# 01-POWER_AC-DC.net
KiCad netlist of a schematic drawn in Altium Designer
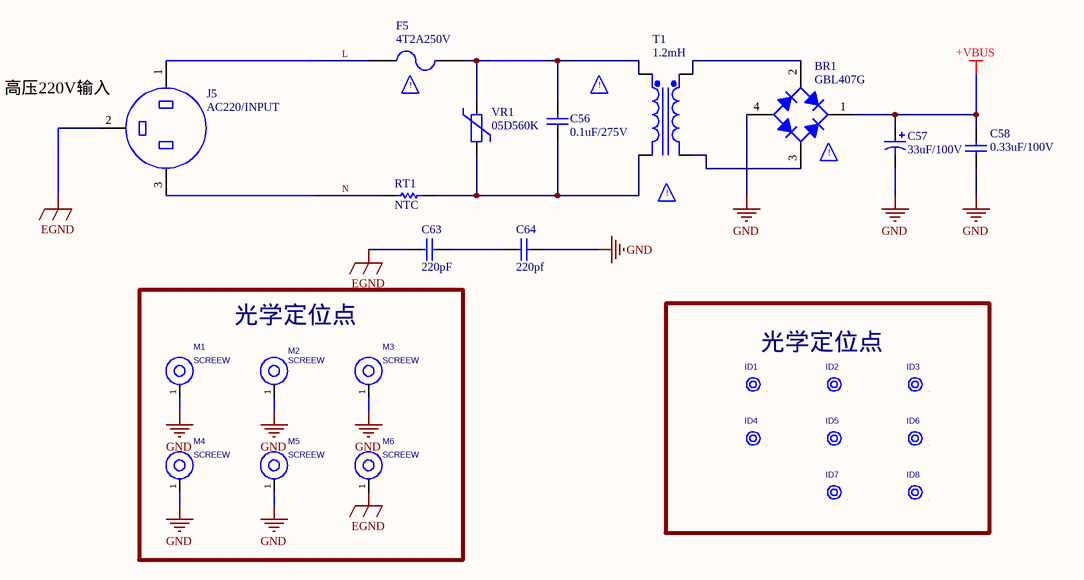
[diagram p0: 01-POWER AC-DC.SchDoc]

(export (version "E")
  (design (tool "Eeschema 10.0.6"))
  (components
    (comp (ref "BR1")
      (value "GBL407G")
      (footprint "GBL407G")
      (description "Full Wave Diode Bridge")
      (fields (field (name "ALTIUM_UNNAMED_1") "GBL407G") (field (name "PUBLISHER") "Altium Limited"))
      (libsource (lib "Miscellaneous Devices") (part "Bridge1"))
    )
    (comp (ref "C56")
      (value "0.1uF/275V")
      (footprint "CBB62-275VAC-104K")
      (description "Capacitor")
      (fields (field (name "Comment") "Cap") (field (name "PUBLISHER") "Altium Limited"))
      (libsource (lib "Miscellaneous Devices") (part "Cap"))
    )
    (comp (ref "C57")
      (value "33uF/100V")
      (footprint "CE16250SH1")
      (description "Polarized Capacitor (Radial)")
      (fields (field (name "PUBLISHER") "Altium Limited"))
      (libsource (lib "Miscellaneous Devices") (part "Cap Pol1"))
    )
    (comp (ref "C58")
      (value "0.33uF/100V")
      (footprint "AF334J1J079L270D9H")
      (description "Capacitor")
      (fields (field (name "Comment") "Cap") (field (name "PUBLISHER") "Altium Limited"))
      (libsource (lib "Miscellaneous Devices") (part "Cap"))
    )
    (comp (ref "C63")
      (value "220pF")
      (footprint "C0805")
      (description "Capacitor")
      (fields (field (name "Comment") "Cap") (field (name "PUBLISHER") "Altium Limited"))
      (libsource (lib "Lib") (part "Cap"))
    )
    (comp (ref "C64")
      (value "220pf")
      (footprint "C0805")
      (description "Capacitor")
      (fields (field (name "Comment") "Cap") (field (name "PUBLISHER") "Altium Limited"))
      (libsource (lib "Lib") (part "Cap"))
    )
    (comp (ref "F5")
      (value "Fuse 2")
      (footprint "4T2A250V")
      (description "Fuse")
      (fields (field (name "ALTIUM_UNNAMED_1") "4T2A250V") (field (name "PUBLISHER") "Altium Limited"))
      (libsource (lib "Miscellaneous Devices") (part "Fuse 2"))
    )
    (comp (ref "ID1")
      (value "LOC")
      (footprint "MARK_1")
      (description "SMT_Locotion")
      (libsource (lib "EMIA-2024-03") (part "LOC"))
    )
    (comp (ref "ID2")
      (value "LOC")
      (footprint "MARK_1")
      (description "SMT_Locotion")
      (libsource (lib "EMIA-2024-03") (part "LOC"))
    )
    (comp (ref "ID3")
      (value "LOC")
      (footprint "MARK_1")
      (description "SMT_Locotion")
      (libsource (lib "EMIA-2024-03") (part "LOC"))
    )
    (comp (ref "ID4")
      (value "LOC")
      (footprint "MARK_1")
      (description "SMT_Locotion")
      (libsource (lib "EMIA-2024-03") (part "LOC"))
    )
    (comp (ref "ID5")
      (value "LOC")
      (footprint "MARK_1")
      (description "SMT_Locotion")
      (libsource (lib "EMIA-2024-03") (part "LOC"))
    )
    (comp (ref "ID6")
      (value "LOC")
      (footprint "MARK_1")
      (description "SMT_Locotion")
      (libsource (lib "EMIA-2024-03") (part "LOC"))
    )
    (comp (ref "ID7")
      (value "LOC")
      (footprint "MARK_1")
      (description "SMT_Locotion")
      (libsource (lib "EMIA-2024-03") (part "LOC"))
    )
    (comp (ref "ID8")
      (value "LOC")
      (footprint "MARK_1")
      (description "SMT_Locotion")
      (libsource (lib "EMIA-2024-03") (part "LOC"))
    )
    (comp (ref "J5")
      (value "AC220/INPUT")
      (footprint "VH-3A")
      (libsource (lib "SCHLIB") (part "AC220/INPUT"))
    )
    (comp (ref "M1")
      (value "SCREEW")
      (footprint "SCREEW")
      (description "MARK Symble")
      (fields (field (name "Comment") "MARK_4") (field (name "CREATED_BY") "CZD"))
      (libsource (lib "*") (part "MARK_4"))
    )
    (comp (ref "M2")
      (value "SCREEW")
      (footprint "SCREEW")
      (description "MARK Symble")
      (fields (field (name "Comment") "MARK_4") (field (name "CREATED_BY") "CZD"))
      (libsource (lib "*") (part "MARK_4"))
    )
    (comp (ref "M3")
      (value "SCREEW")
      (footprint "SCREEW")
      (description "MARK Symble")
      (fields (field (name "Comment") "MARK_4") (field (name "CREATED_BY") "CZD"))
      (libsource (lib "*") (part "MARK_4"))
    )
    (comp (ref "M4")
      (value "SCREEW")
      (footprint "SCREEW")
      (description "MARK Symble")
      (fields (field (name "Comment") "MARK_4") (field (name "CREATED_BY") "CZD"))
      (libsource (lib "*") (part "MARK_4"))
    )
    (comp (ref "M5")
      (value "SCREEW")
      (footprint "SCREEW")
      (description "MARK Symble")
      (fields (field (name "Comment") "MARK_4") (field (name "CREATED_BY") "CZD"))
      (libsource (lib "*") (part "MARK_4"))
    )
    (comp (ref "M6")
      (value "SCREEW")
      (footprint "SCREEW")
      (description "MARK Symble")
      (fields (field (name "Comment") "MARK_4") (field (name "CREATED_BY") "CZD"))
      (libsource (lib "*") (part "MARK_4"))
    )
    (comp (ref "RT1")
      (value "NTC")
      (footprint "NTC-10D9")
      (description "Resistor")
      (fields (field (name "PUBLISHER") "Altium Limited"))
      (libsource (lib "Miscellaneous Devices") (part "Res1"))
    )
    (comp (ref "T1")
      (value "1.2mH")
      (footprint "UU1014")
      (description "Transformer (Equivalent Circuit Model)")
      (fields (field (name "PUBLISHER") "Altium Limited"))
      (libsource (lib "Miscellaneous Devices") (part "Trans Eq"))
    )
    (comp (ref "VR1") (value "05D560K") (footprint "RUEF400") (libsource (lib "SCHLIB") (part "VR 561K")))
  )
  (nets
    (net (code "1") (name "+VBUS") (class "Default")
      (node (ref "BR1") (pin "1") (pinfunction "K_1") (pintype "passive"))
      (node (ref "C57") (pin "1") (pinfunction "1_1") (pintype "passive"))
      (node (ref "C58") (pin "2") (pinfunction "2_2") (pintype "passive"))
    )
    (net (code "2") (name "/L") (class "Default")
      (node (ref "F5") (pin "1") (pinfunction "1_1") (pintype "passive"))
      (node (ref "J5") (pin "1") (pinfunction "1_1") (pintype "passive"))
    )
    (net (code "3") (name "/N") (class "Default")
      (node (ref "J5") (pin "3") (pinfunction "2_3") (pintype "passive"))
      (node (ref "RT1") (pin "1") (pinfunction "1_1") (pintype "passive"))
    )
    (net (code "4") (name "EGND") (class "Default")
      (node (ref "C63") (pin "1") (pinfunction "1_1") (pintype "passive"))
      (node (ref "J5") (pin "2") (pinfunction "3_2") (pintype "passive"))
      (node (ref "M6") (pin "1") (pinfunction "1_1") (pintype "passive"))
    )
    (net (code "5") (name "GND") (class "Default")
      (node (ref "BR1") (pin "4") (pinfunction "A_4") (pintype "passive"))
      (node (ref "C57") (pin "2") (pinfunction "2_2") (pintype "passive"))
      (node (ref "C58") (pin "1") (pinfunction "1_1") (pintype "passive"))
      (node (ref "C64") (pin "2") (pinfunction "2_2") (pintype "passive"))
      (node (ref "M1") (pin "1") (pinfunction "1_1") (pintype "passive"))
      (node (ref "M2") (pin "1") (pinfunction "1_1") (pintype "passive"))
      (node (ref "M3") (pin "1") (pinfunction "1_1") (pintype "passive"))
      (node (ref "M4") (pin "1") (pinfunction "1_1") (pintype "passive"))
      (node (ref "M5") (pin "1") (pinfunction "1_1") (pintype "passive"))
    )
    (net (code "6") (name "Net-(C63-Pad2)") (class "Default")
      (node (ref "C63") (pin "2") (pinfunction "2_2") (pintype "passive"))
      (node (ref "C64") (pin "1") (pinfunction "1_1") (pintype "passive"))
    )
    (net (code "7") (name "Net-(T1-Pri+)") (class "Default")
      (node (ref "C56") (pin "1") (pinfunction "1_1") (pintype "passive"))
      (node (ref "F5") (pin "2") (pinfunction "2_2") (pintype "passive"))
      (node (ref "T1") (pin "1") (pinfunction "Pri+_1") (pintype "passive"))
      (node (ref "VR1") (pin "2") (pinfunction "2_2") (pintype "passive"))
    )
    (net (code "8") (name "Net-(T1-Pri-)") (class "Default")
      (node (ref "C56") (pin "2") (pinfunction "2_2") (pintype "passive"))
      (node (ref "RT1") (pin "2") (pinfunction "2_2") (pintype "passive"))
      (node (ref "T1") (pin "2") (pinfunction "Pri-_2") (pintype "passive"))
      (node (ref "VR1") (pin "1") (pinfunction "1_1") (pintype "passive"))
    )
    (net (code "9") (name "Net-(T1-Sec+)") (class "Default")
      (node (ref "BR1") (pin "2") (pinfunction "C_2") (pintype "passive"))
      (node (ref "T1") (pin "3") (pinfunction "Sec+_3") (pintype "passive"))
    )
    (net (code "10") (name "Net-(T1-Sec-)") (class "Default")
      (node (ref "BR1") (pin "3") (pinfunction "C_3") (pintype "passive"))
      (node (ref "T1") (pin "4") (pinfunction "Sec-_4") (pintype "passive"))
    )
    (net (code "11") (name "unconnected-(ID1-Pad1)") (class "Default")
      (node (ref "ID1") (pin "1") (pinfunction "1_1") (pintype "passive"))
    )
    (net (code "12") (name "unconnected-(ID2-Pad1)") (class "Default")
      (node (ref "ID2") (pin "1") (pinfunction "1_1") (pintype "passive"))
    )
    (net (code "13") (name "unconnected-(ID3-Pad1)") (class "Default")
      (node (ref "ID3") (pin "1") (pinfunction "1_1") (pintype "passive"))
    )
    (net (code "14") (name "unconnected-(ID4-Pad1)") (class "Default")
      (node (ref "ID4") (pin "1") (pinfunction "1_1") (pintype "passive"))
    )
    (net (code "15") (name "unconnected-(ID5-Pad1)") (class "Default")
      (node (ref "ID5") (pin "1") (pinfunction "1_1") (pintype "passive"))
    )
    (net (code "16") (name "unconnected-(ID6-Pad1)") (class "Default")
      (node (ref "ID6") (pin "1") (pinfunction "1_1") (pintype "passive"))
    )
    (net (code "17") (name "unconnected-(ID7-Pad1)") (class "Default")
      (node (ref "ID7") (pin "1") (pinfunction "1_1") (pintype "passive"))
    )
    (net (code "18") (name "unconnected-(ID8-Pad1)") (class "Default")
      (node (ref "ID8") (pin "1") (pinfunction "1_1") (pintype "passive"))
    )
  )
)
